# RGB_Video_Output.net
KiCad netlist of a schematic drawn in Altium Designer
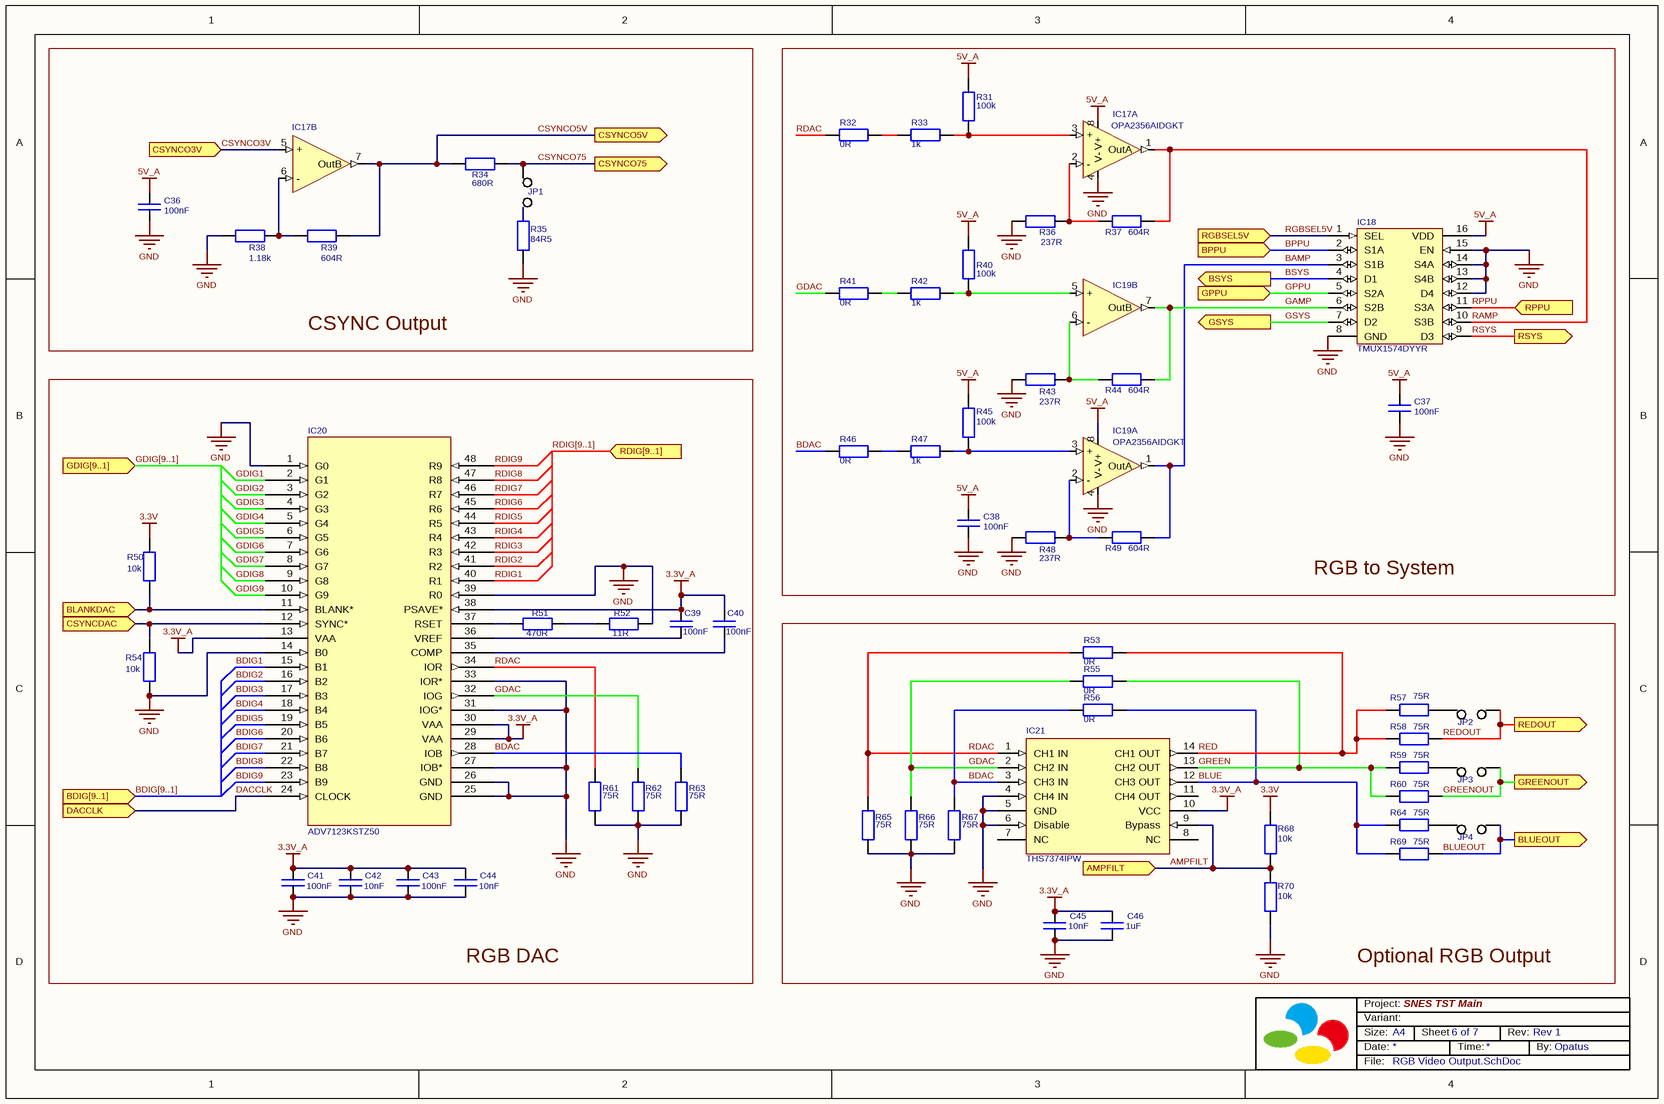
[diagram p0: RGB Video Output.SchDoc]

(export (version "E")
  (design (tool "Eeschema 10.0.6"))
  (components
    (comp (ref "C36")
      (value "100nF")
      (footprint "Cap_0402_Chip")
      (fields
        (field (name "TOLERANCE") "±20%")
        (field (name "Comment") "Ceramic Capacitor 100nF 10V ±20% X7R 0402")
      )
      (libsource (lib "PCB") (part "Capacitor"))
    )
    (comp (ref "C37")
      (value "100nF")
      (footprint "Cap_0402_Chip")
      (fields
        (field (name "TOLERANCE") "±20%")
        (field (name "Comment") "Ceramic Capacitor 100nF 10V ±20% X7R 0402")
      )
      (libsource (lib "PCB") (part "Capacitor"))
    )
    (comp (ref "C38")
      (value "100nF")
      (footprint "Cap_0402_Chip")
      (fields
        (field (name "TOLERANCE") "±20%")
        (field (name "Comment") "Ceramic Capacitor 100nF 10V ±20% X7R 0402")
      )
      (libsource (lib "PCB") (part "Capacitor"))
    )
    (comp (ref "C39")
      (value "100nF")
      (footprint "Cap_0402_Chip")
      (fields
        (field (name "TOLERANCE") "±20%")
        (field (name "Comment") "Ceramic Capacitor 100nF 10V ±20% X7R 0402")
      )
      (libsource (lib "PCB") (part "Capacitor"))
    )
    (comp (ref "C40")
      (value "100nF")
      (footprint "Cap_0402_Chip")
      (fields
        (field (name "TOLERANCE") "±20%")
        (field (name "Comment") "Ceramic Capacitor 100nF 10V ±20% X7R 0402")
      )
      (libsource (lib "PCB") (part "Capacitor"))
    )
    (comp (ref "C41")
      (value "100nF")
      (footprint "Cap_0402_Chip")
      (fields
        (field (name "TOLERANCE") "±20%")
        (field (name "Comment") "Ceramic Capacitor 100nF 10V ±20% X7R 0402")
      )
      (libsource (lib "PCB") (part "Capacitor"))
    )
    (comp (ref "C42")
      (value "10nF")
      (footprint "Cap_0402_Chip")
      (fields
        (field (name "TOLERANCE") "±20%")
        (field (name "Comment") "Ceramic Capacitor 10nF 10V ±20% X7R 0402")
      )
      (libsource (lib "PCB") (part "Capacitor"))
    )
    (comp (ref "C43")
      (value "100nF")
      (footprint "Cap_0402_Chip")
      (fields
        (field (name "TOLERANCE") "±20%")
        (field (name "Comment") "Ceramic Capacitor 100nF 10V ±20% X7R 0402")
      )
      (libsource (lib "PCB") (part "Capacitor"))
    )
    (comp (ref "C44")
      (value "10nF")
      (footprint "Cap_0402_Chip")
      (fields
        (field (name "TOLERANCE") "±20%")
        (field (name "Comment") "Ceramic Capacitor 10nF 10V ±20% X7R 0402")
      )
      (libsource (lib "PCB") (part "Capacitor"))
    )
    (comp (ref "C45")
      (value "10nF")
      (footprint "Cap_0402_Chip")
      (fields
        (field (name "TOLERANCE") "±20%")
        (field (name "Comment") "Ceramic Capacitor 10nF 10V ±20% X7R 0402")
      )
      (libsource (lib "PCB") (part "Capacitor"))
    )
    (comp (ref "C46")
      (value "1uF")
      (footprint "Cap_0603_Chip")
      (fields
        (field (name "TOLERANCE") "±20%")
        (field (name "Comment") "Ceramic Capacitor 1uF 10V ±20% X7R 0603")
      )
      (libsource (lib "PCB") (part "Capacitor"))
    )
    (comp (ref "IC17")
      (value "OPA2356")
      (footprint "MSOP8")
      (fields
        (field (name "MANUFACTURER") "Texas Instruments")
        (field (name "MANUFACTURER_PART_NUMBER") "OPA2356AIDGKT")
      )
      (libsource (lib "PCB") (part "OPA2356"))
    )
    (comp (ref "IC18")
      (value "TMUX1574")
      (footprint "SOT-23THIN16")
      (description "SPDT 4 Ch")
      (fields
        (field (name "MANUFACTURER") "Texas Instruments")
        (field (name "MANUFACTURER_PART_NUMBER") "TMUX1574DYYR")
      )
      (libsource (lib "PCB") (part "TMUX1574"))
    )
    (comp (ref "IC19")
      (value "OPA2356")
      (footprint "MSOP8")
      (fields
        (field (name "MANUFACTURER") "Texas Instruments")
        (field (name "MANUFACTURER_PART_NUMBER") "OPA2356AIDGKT")
      )
      (libsource (lib "PCB") (part "OPA2356"))
    )
    (comp (ref "IC20")
      (value "ADV7123")
      (footprint "ST_48_ADI")
      (description "10Bit Video DAC")
      (fields
        (field (name "MANUFACTURER") "Analog Devices Inc")
        (field (name "MANUFACTURER_PART_NUMBER") "ADV7123KSTZ50")
        (field (name "COPYRIGHT") "Copyright (C) 2018 Accelerated Designs. All rights reserved")
      )
      (libsource (lib "PCB") (part "ADV7123KSTZ140"))
    )
    (comp (ref "IC21")
      (value "THS7374")
      (footprint "TSSOP14")
      (fields
        (field (name "MANUFACTURER") "Texas Instruments")
        (field (name "MANUFACTURER_PART_NUMBER") "THS7374IPW")
      )
      (libsource (lib "PCB") (part "THS7374"))
    )
    (comp (ref "JP1") (value "Jumper") (footprint "Jumper") (libsource (lib "PCB") (part "Jumper")))
    (comp (ref "JP2") (value "Jumper") (footprint "Jumper") (libsource (lib "PCB") (part "Jumper")))
    (comp (ref "JP3") (value "Jumper") (footprint "Jumper") (libsource (lib "PCB") (part "Jumper")))
    (comp (ref "JP4") (value "Jumper") (footprint "Jumper") (libsource (lib "PCB") (part "Jumper")))
    (comp (ref "R31")
      (value "100k")
      (footprint "Res_0402_Chip")
      (fields (field (name "TOLERANCE") "±1%") (field (name "Comment") "Resistor 100k 0402 ±1%"))
      (libsource (lib "") (part "R_2"))
    )
    (comp (ref "R32")
      (value "0R")
      (footprint "Res_0402_Chip")
      (fields (field (name "Comment") "Resistor 0R 0402 "))
      (libsource (lib "PCB") (part "R"))
    )
    (comp (ref "R33")
      (value "1k")
      (footprint "Res_0402_Chip")
      (fields (field (name "TOLERANCE") "±1%") (field (name "Comment") "Resistor 1k 0402 ±1%"))
      (libsource (lib "PCB") (part "R"))
    )
    (comp (ref "R34")
      (value "680R")
      (footprint "Res_0603_Chip")
      (fields (field (name "TOLERANCE") "±1%") (field (name "Comment") "Resistor 680R 0603 ±1%"))
      (libsource (lib "") (part "R_1"))
    )
    (comp (ref "R35")
      (value "84R5")
      (footprint "Res_0402_Chip")
      (fields (field (name "TOLERANCE") "±1%") (field (name "Comment") "Resistor 84R5 0402 ±1%"))
      (libsource (lib "") (part "R_2"))
    )
    (comp (ref "R36")
      (value "237R")
      (footprint "Res_0402_Chip")
      (fields (field (name "TOLERANCE") "±1%") (field (name "Comment") "Resistor 237R 0402 ±1%"))
      (libsource (lib "") (part "R_1"))
    )
    (comp (ref "R37")
      (value "604R")
      (footprint "Res_0402_Chip")
      (fields (field (name "TOLERANCE") "±1%") (field (name "Comment") "Resistor 604R 0402 ±1%"))
      (libsource (lib "") (part "R_1"))
    )
    (comp (ref "R38")
      (value "1.18k")
      (footprint "Res_0402_Chip")
      (fields (field (name "TOLERANCE") "±1%") (field (name "Comment") "Resistor 1.18k 0402 ±1%"))
      (libsource (lib "") (part "R_1"))
    )
    (comp (ref "R39")
      (value "604R")
      (footprint "Res_0402_Chip")
      (fields (field (name "TOLERANCE") "±1%") (field (name "Comment") "Resistor 604R 0402 ±1%"))
      (libsource (lib "PCB") (part "R"))
    )
    (comp (ref "R40")
      (value "100k")
      (footprint "Res_0402_Chip")
      (fields (field (name "TOLERANCE") "±1%") (field (name "Comment") "Resistor 100k 0402 ±1%"))
      (libsource (lib "") (part "R_2"))
    )
    (comp (ref "R41")
      (value "0R")
      (footprint "Res_0402_Chip")
      (fields (field (name "Comment") "Resistor 0R 0402 "))
      (libsource (lib "PCB") (part "R"))
    )
    (comp (ref "R42")
      (value "1k")
      (footprint "Res_0402_Chip")
      (fields (field (name "TOLERANCE") "±1%") (field (name "Comment") "Resistor 1k 0402 ±1%"))
      (libsource (lib "PCB") (part "R"))
    )
    (comp (ref "R43")
      (value "237R")
      (footprint "Res_0402_Chip")
      (fields (field (name "TOLERANCE") "±1%") (field (name "Comment") "Resistor 237R 0402 ±1%"))
      (libsource (lib "") (part "R_1"))
    )
    (comp (ref "R44")
      (value "604R")
      (footprint "Res_0402_Chip")
      (fields (field (name "TOLERANCE") "±1%") (field (name "Comment") "Resistor 604R 0402 ±1%"))
      (libsource (lib "PCB") (part "R"))
    )
    (comp (ref "R45")
      (value "100k")
      (footprint "Res_0402_Chip")
      (fields (field (name "TOLERANCE") "±1%") (field (name "Comment") "Resistor 100k 0402 ±1%"))
      (libsource (lib "") (part "R_2"))
    )
    (comp (ref "R46")
      (value "0R")
      (footprint "Res_0402_Chip")
      (fields (field (name "Comment") "Resistor 0R 0402 "))
      (libsource (lib "PCB") (part "R"))
    )
    (comp (ref "R47")
      (value "1k")
      (footprint "Res_0402_Chip")
      (fields (field (name "TOLERANCE") "±1%") (field (name "Comment") "Resistor 1k 0402 ±1%"))
      (libsource (lib "PCB") (part "R"))
    )
    (comp (ref "R48")
      (value "237R")
      (footprint "Res_0402_Chip")
      (fields (field (name "TOLERANCE") "±1%") (field (name "Comment") "Resistor 237R 0402 ±1%"))
      (libsource (lib "PCB") (part "R"))
    )
    (comp (ref "R49")
      (value "604R")
      (footprint "Res_0402_Chip")
      (fields (field (name "TOLERANCE") "±1%") (field (name "Comment") "Resistor 604R 0402 ±1%"))
      (libsource (lib "") (part "R_1"))
    )
    (comp (ref "R50")
      (value "10k")
      (footprint "Res_0402_Chip")
      (fields (field (name "TOLERANCE") "±1%") (field (name "Comment") "Resistor 10k 0402 ±1%"))
      (libsource (lib "") (part "R_2"))
    )
    (comp (ref "R51")
      (value "470R")
      (footprint "Res_0402_Chip")
      (fields (field (name "TOLERANCE") "±1%") (field (name "Comment") "Resistor 470R 0402 ±1%"))
      (libsource (lib "") (part "R_1"))
    )
    (comp (ref "R52")
      (value "11R")
      (footprint "Res_0402_Chip")
      (fields (field (name "TOLERANCE") "±1%") (field (name "Comment") "Resistor 11R 0402 ±1%"))
      (libsource (lib "") (part "R_1"))
    )
    (comp (ref "R53")
      (value "0R")
      (footprint "Res_0402_Chip")
      (fields (field (name "Comment") "Resistor 0R 0402 "))
      (libsource (lib "PCB") (part "R"))
    )
    (comp (ref "R54")
      (value "10k")
      (footprint "Res_0402_Chip")
      (fields (field (name "TOLERANCE") "±1%") (field (name "Comment") "Resistor 10k 0402 ±1%"))
      (libsource (lib "") (part "R_2"))
    )
    (comp (ref "R55")
      (value "0R")
      (footprint "Res_0402_Chip")
      (fields (field (name "Comment") "Resistor 0R 0402 "))
      (libsource (lib "PCB") (part "R"))
    )
    (comp (ref "R56")
      (value "0R")
      (footprint "Res_0402_Chip")
      (fields (field (name "Comment") "Resistor 0R 0402 "))
      (libsource (lib "PCB") (part "R"))
    )
    (comp (ref "R57")
      (value "75R")
      (footprint "Res_0603_Chip")
      (fields (field (name "TOLERANCE") "±1%") (field (name "Comment") "Resistor 75R 0603 ±1%"))
      (libsource (lib "") (part "R_1"))
    )
    (comp (ref "R58")
      (value "75R")
      (footprint "Res_0603_Chip")
      (fields (field (name "TOLERANCE") "±1%") (field (name "Comment") "Resistor 75R 0603 ±1%"))
      (libsource (lib "") (part "R_1"))
    )
    (comp (ref "R59")
      (value "75R")
      (footprint "Res_0603_Chip")
      (fields (field (name "TOLERANCE") "±1%") (field (name "Comment") "Resistor 75R 0603 ±1%"))
      (libsource (lib "") (part "R_1"))
    )
    (comp (ref "R60")
      (value "75R")
      (footprint "Res_0603_Chip")
      (fields (field (name "TOLERANCE") "±1%") (field (name "Comment") "Resistor 75R 0603 ±1%"))
      (libsource (lib "") (part "R_1"))
    )
    (comp (ref "R61")
      (value "75R")
      (footprint "Res_0402_Chip")
      (fields (field (name "TOLERANCE") "±1%") (field (name "Comment") "Resistor 75R 0402 ±1%"))
      (libsource (lib "") (part "R_2"))
    )
    (comp (ref "R62")
      (value "75R")
      (footprint "Res_0402_Chip")
      (fields (field (name "TOLERANCE") "±1%") (field (name "Comment") "Resistor 75R 0402 ±1%"))
      (libsource (lib "") (part "R_2"))
    )
    (comp (ref "R63")
      (value "75R")
      (footprint "Res_0402_Chip")
      (fields (field (name "TOLERANCE") "±1%") (field (name "Comment") "Resistor 75R 0402 ±1%"))
      (libsource (lib "") (part "R_2"))
    )
    (comp (ref "R64")
      (value "75R")
      (footprint "Res_0603_Chip")
      (fields (field (name "TOLERANCE") "±1%") (field (name "Comment") "Resistor 75R 0603 ±1%"))
      (libsource (lib "") (part "R_1"))
    )
    (comp (ref "R65")
      (value "75R")
      (footprint "Res_0402_Chip")
      (fields (field (name "TOLERANCE") "±1%") (field (name "Comment") "Resistor 75R 0402 ±1%"))
      (libsource (lib "") (part "R_2"))
    )
    (comp (ref "R66")
      (value "75R")
      (footprint "Res_0402_Chip")
      (fields (field (name "TOLERANCE") "±1%") (field (name "Comment") "Resistor 75R 0402 ±1%"))
      (libsource (lib "") (part "R_2"))
    )
    (comp (ref "R67")
      (value "75R")
      (footprint "Res_0402_Chip")
      (fields (field (name "TOLERANCE") "±1%") (field (name "Comment") "Resistor 75R 0402 ±1%"))
      (libsource (lib "") (part "R_2"))
    )
    (comp (ref "R68")
      (value "10k")
      (footprint "Res_0402_Chip")
      (fields (field (name "TOLERANCE") "±1%") (field (name "Comment") "Resistor 10k 0402 ±1%"))
      (libsource (lib "") (part "R_3"))
    )
    (comp (ref "R69")
      (value "75R")
      (footprint "Res_0603_Chip")
      (fields (field (name "TOLERANCE") "±1%") (field (name "Comment") "Resistor 75R 0603 ±1%"))
      (libsource (lib "") (part "R_1"))
    )
    (comp (ref "R70")
      (value "10k")
      (footprint "Res_0402_Chip")
      (fields (field (name "TOLERANCE") "±1%") (field (name "Comment") "Resistor 10k 0402 ±1%"))
      (libsource (lib "") (part "R_3"))
    )
  )
  (nets
    (net (code "1") (name "/AMPFILT") (class "Default")
      (node (ref "IC21") (pin "9") (pinfunction "Bypass_9") (pintype "input"))
      (node (ref "R68") (pin "2") (pintype "passive"))
      (node (ref "R70") (pin "1") (pintype "passive"))
    )
    (net (code "2") (name "/BAMP") (class "Default")
      (node (ref "IC18") (pin "3") (pinfunction "S1B_3") (pintype "bidirectional"))
      (node (ref "IC19") (pin "1") (pinfunction "OutA_1") (pintype "output"))
      (node (ref "R49") (pin "2") (pintype "passive"))
    )
    (net (code "3") (name "/BDAC") (class "Default")
      (node (ref "IC20") (pin "28") (pinfunction "IOB_28") (pintype "output"))
      (node (ref "IC21") (pin "3") (pinfunction "CH3_IN_3") (pintype "input"))
      (node (ref "R46") (pin "2") (pintype "passive"))
      (node (ref "R56") (pin "2") (pintype "passive"))
      (node (ref "R63") (pin "2") (pintype "passive"))
      (node (ref "R67") (pin "2") (pintype "passive"))
    )
    (net (code "4") (name "/BDIG1") (class "Default")
      (node (ref "IC20") (pin "15") (pinfunction "B1_15") (pintype "input"))
    )
    (net (code "5") (name "/BDIG2") (class "Default")
      (node (ref "IC20") (pin "16") (pinfunction "B2_16") (pintype "input"))
    )
    (net (code "6") (name "/BDIG3") (class "Default")
      (node (ref "IC20") (pin "17") (pinfunction "B3_17") (pintype "input"))
    )
    (net (code "7") (name "/BDIG4") (class "Default")
      (node (ref "IC20") (pin "18") (pinfunction "B4_18") (pintype "input"))
    )
    (net (code "8") (name "/BDIG5") (class "Default")
      (node (ref "IC20") (pin "19") (pinfunction "B5_19") (pintype "input"))
    )
    (net (code "9") (name "/BDIG6") (class "Default")
      (node (ref "IC20") (pin "20") (pinfunction "B6_20") (pintype "input"))
    )
    (net (code "10") (name "/BDIG7") (class "Default")
      (node (ref "IC20") (pin "21") (pinfunction "B7_21") (pintype "input"))
    )
    (net (code "11") (name "/BDIG8") (class "Default")
      (node (ref "IC20") (pin "22") (pinfunction "B8_22") (pintype "input"))
    )
    (net (code "12") (name "/BDIG9") (class "Default")
      (node (ref "IC20") (pin "23") (pinfunction "B9_23") (pintype "input"))
    )
    (net (code "14") (name "/BLANKDAC") (class "Default")
      (node (ref "IC20") (pin "11") (pinfunction "BLANK*_11") (pintype "input"))
      (node (ref "R50") (pin "1") (pintype "passive"))
    )
    (net (code "15") (name "/BLUE") (class "Default")
      (node (ref "IC21") (pin "12") (pinfunction "CH3_OUT_12") (pintype "output"))
      (node (ref "R56") (pin "1") (pintype "passive"))
      (node (ref "R64") (pin "1") (pintype "passive"))
      (node (ref "R69") (pin "1") (pintype "passive"))
    )
    (net (code "16") (name "/BLUEOUT") (class "Default")
      (node (ref "JP4") (pin "1") (pinfunction "0_1") (pintype "passive"))
      (node (ref "R69") (pin "2") (pintype "passive"))
    )
    (net (code "17") (name "/BPPU") (class "Default")
      (node (ref "IC18") (pin "2") (pinfunction "S1A_2") (pintype "bidirectional"))
    )
    (net (code "18") (name "/BSYS") (class "Default")
      (node (ref "IC18") (pin "4") (pinfunction "D1_4") (pintype "bidirectional"))
    )
    (net (code "19") (name "/CSYNCDAC") (class "Default")
      (node (ref "IC20") (pin "12") (pinfunction "SYNC*_12") (pintype "input"))
      (node (ref "R54") (pin "2") (pintype "passive"))
    )
    (net (code "20") (name "/CSYNCO3V") (class "Default")
      (node (ref "IC17") (pin "5") (pinfunction "+_5") (pintype "input"))
    )
    (net (code "21") (name "/CSYNCO5V") (class "Default")
      (node (ref "IC17") (pin "7") (pinfunction "OutB_7") (pintype "output"))
      (node (ref "R34") (pin "1") (pintype "passive"))
      (node (ref "R39") (pin "1") (pintype "passive"))
    )
    (net (code "22") (name "/CSYNCO75") (class "Default")
      (node (ref "JP1") (pin "1") (pinfunction "0_1") (pintype "passive"))
      (node (ref "R34") (pin "2") (pintype "passive"))
    )
    (net (code "23") (name "/DACCLK") (class "Default")
      (node (ref "IC20") (pin "24") (pinfunction "CLOCK_24") (pintype "input"))
    )
    (net (code "24") (name "/GAMP") (class "Default")
      (node (ref "IC18") (pin "6") (pinfunction "S2B_6") (pintype "bidirectional"))
      (node (ref "IC19") (pin "7") (pinfunction "OutB_7") (pintype "output"))
      (node (ref "R44") (pin "1") (pintype "passive"))
    )
    (net (code "25") (name "/GDAC") (class "Default")
      (node (ref "IC20") (pin "32") (pinfunction "IOG_32") (pintype "output"))
      (node (ref "IC21") (pin "2") (pinfunction "CH2_IN_2") (pintype "input"))
      (node (ref "R41") (pin "2") (pintype "passive"))
      (node (ref "R55") (pin "2") (pintype "passive"))
      (node (ref "R62") (pin "2") (pintype "passive"))
      (node (ref "R66") (pin "2") (pintype "passive"))
    )
    (net (code "26") (name "/GDIG1") (class "Default")
      (node (ref "IC20") (pin "2") (pinfunction "G1_2") (pintype "input"))
    )
    (net (code "27") (name "/GDIG2") (class "Default")
      (node (ref "IC20") (pin "3") (pinfunction "G2_3") (pintype "input"))
    )
    (net (code "28") (name "/GDIG3") (class "Default")
      (node (ref "IC20") (pin "4") (pinfunction "G3_4") (pintype "input"))
    )
    (net (code "29") (name "/GDIG4") (class "Default")
      (node (ref "IC20") (pin "5") (pinfunction "G4_5") (pintype "input"))
    )
    (net (code "30") (name "/GDIG5") (class "Default")
      (node (ref "IC20") (pin "6") (pinfunction "G5_6") (pintype "input"))
    )
    (net (code "31") (name "/GDIG6") (class "Default")
      (node (ref "IC20") (pin "7") (pinfunction "G6_7") (pintype "input"))
    )
    (net (code "32") (name "/GDIG7") (class "Default")
      (node (ref "IC20") (pin "8") (pinfunction "G7_8") (pintype "input"))
    )
    (net (code "33") (name "/GDIG8") (class "Default")
      (node (ref "IC20") (pin "9") (pinfunction "G8_9") (pintype "input"))
    )
    (net (code "34") (name "/GDIG9") (class "Default")
      (node (ref "IC20") (pin "10") (pinfunction "G9_10") (pintype "input"))
    )
    (net (code "36") (name "/GPPU") (class "Default")
      (node (ref "IC18") (pin "5") (pinfunction "S2A_5") (pintype "bidirectional"))
    )
    (net (code "37") (name "/GREEN") (class "Default")
      (node (ref "IC21") (pin "13") (pinfunction "CH2_OUT_13") (pintype "output"))
      (node (ref "R55") (pin "1") (pintype "passive"))
      (node (ref "R59") (pin "1") (pintype "passive"))
      (node (ref "R60") (pin "1") (pintype "passive"))
    )
    (net (code "38") (name "/GREENOUT") (class "Default")
      (node (ref "JP3") (pin "1") (pinfunction "0_1") (pintype "passive"))
      (node (ref "R60") (pin "2") (pintype "passive"))
    )
    (net (code "39") (name "/GSYS") (class "Default")
      (node (ref "IC18") (pin "7") (pinfunction "D2_7") (pintype "bidirectional"))
    )
    (net (code "40") (name "/RAMP") (class "Default")
      (node (ref "IC17") (pin "1") (pinfunction "OutA_1") (pintype "output"))
      (node (ref "IC18") (pin "10") (pinfunction "S3B_10") (pintype "bidirectional"))
      (node (ref "R37") (pin "2") (pintype "passive"))
    )
    (net (code "41") (name "/RDAC") (class "Default")
      (node (ref "IC20") (pin "34") (pinfunction "IOR_34") (pintype "output"))
      (node (ref "IC21") (pin "1") (pinfunction "CH1_IN_1") (pintype "input"))
      (node (ref "R32") (pin "2") (pintype "passive"))
      (node (ref "R53") (pin "2") (pintype "passive"))
      (node (ref "R61") (pin "2") (pintype "passive"))
      (node (ref "R65") (pin "2") (pintype "passive"))
    )
    (net (code "42") (name "/RDIG1") (class "Default")
      (node (ref "IC20") (pin "40") (pinfunction "R1_40") (pintype "input"))
    )
    (net (code "43") (name "/RDIG2") (class "Default")
      (node (ref "IC20") (pin "41") (pinfunction "R2_41") (pintype "input"))
    )
    (net (code "44") (name "/RDIG3") (class "Default")
      (node (ref "IC20") (pin "42") (pinfunction "R3_42") (pintype "input"))
    )
    (net (code "45") (name "/RDIG4") (class "Default")
      (node (ref "IC20") (pin "43") (pinfunction "R4_43") (pintype "input"))
    )
    (net (code "46") (name "/RDIG5") (class "Default")
      (node (ref "IC20") (pin "44") (pinfunction "R5_44") (pintype "input"))
    )
    (net (code "47") (name "/RDIG6") (class "Default")
      (node (ref "IC20") (pin "45") (pinfunction "R6_45") (pintype "input"))
    )
    (net (code "48") (name "/RDIG7") (class "Default")
      (node (ref "IC20") (pin "46") (pinfunction "R7_46") (pintype "input"))
    )
    (net (code "49") (name "/RDIG8") (class "Default")
      (node (ref "IC20") (pin "47") (pinfunction "R8_47") (pintype "input"))
    )
    (net (code "50") (name "/RDIG9") (class "Default")
      (node (ref "IC20") (pin "48") (pinfunction "R9_48") (pintype "input"))
    )
    (net (code "52") (name "/RED") (class "Default")
      (node (ref "IC21") (pin "14") (pinfunction "CH1_OUT_14") (pintype "output"))
      (node (ref "R53") (pin "1") (pintype "passive"))
      (node (ref "R57") (pin "1") (pintype "passive"))
      (node (ref "R58") (pin "1") (pintype "passive"))
    )
    (net (code "53") (name "/REDOUT") (class "Default")
      (node (ref "JP2") (pin "1") (pinfunction "0_1") (pintype "passive"))
      (node (ref "R58") (pin "2") (pintype "passive"))
    )
    (net (code "54") (name "/RGBSEL5V") (class "Default")
      (node (ref "IC18") (pin "1") (pinfunction "SEL_1") (pintype "input"))
    )
    (net (code "55") (name "/RPPU") (class "Default")
      (node (ref "IC18") (pin "11") (pinfunction "S3A_11") (pintype "bidirectional"))
    )
    (net (code "56") (name "/RSYS") (class "Default")
      (node (ref "IC18") (pin "9") (pinfunction "D3_9") (pintype "bidirectional"))
    )
    (net (code "57") (name "3.3V") (class "Default")
      (node (ref "R50") (pin "2") (pintype "passive"))
      (node (ref "R68") (pin "1") (pintype "passive"))
    )
    (net (code "58") (name "3.3V_A") (class "Default")
      (node (ref "C39") (pin "1") (pintype "passive"))
      (node (ref "C40") (pin "1") (pintype "passive"))
      (node (ref "C41") (pin "2") (pintype "passive"))
      (node (ref "C42") (pin "2") (pintype "passive"))
      (node (ref "C43") (pin "2") (pintype "passive"))
      (node (ref "C44") (pin "2") (pintype "passive"))
      (node (ref "C45") (pin "2") (pintype "passive"))
      (node (ref "C46") (pin "2") (pintype "passive"))
      (node (ref "IC20") (pin "13") (pinfunction "VAA_13") (pintype "power_in"))
      (node (ref "IC20") (pin "29") (pinfunction "VAA_29") (pintype "power_in"))
      (node (ref "IC20") (pin "30") (pinfunction "VAA_30") (pintype "power_in"))
      (node (ref "IC20") (pin "38") (pinfunction "PSAVE*_38") (pintype "input"))
      (node (ref "IC21") (pin "10") (pinfunction "VCC_10") (pintype "power_in"))
    )
    (net (code "59") (name "5V_A") (class "Default")
      (node (ref "C36") (pin "1") (pintype "passive"))
      (node (ref "C37") (pin "1") (pintype "passive"))
      (node (ref "C38") (pin "1") (pintype "passive"))
      (node (ref "IC17") (pin "8") (pinfunction "V+_8") (pintype "power_in"))
      (node (ref "IC18") (pin "16") (pinfunction "VDD_16") (pintype "power_in"))
      (node (ref "IC19") (pin "8") (pinfunction "V+_8") (pintype "power_in"))
      (node (ref "R31") (pin "2") (pintype "passive"))
      (node (ref "R40") (pin "2") (pintype "passive"))
      (node (ref "R45") (pin "2") (pintype "passive"))
    )
    (net (code "60") (name "GND") (class "Default")
      (node (ref "C36") (pin "2") (pintype "passive"))
      (node (ref "C37") (pin "2") (pintype "passive"))
      (node (ref "C38") (pin "2") (pintype "passive"))
      (node (ref "C41") (pin "1") (pintype "passive"))
      (node (ref "C42") (pin "1") (pintype "passive"))
      (node (ref "C43") (pin "1") (pintype "passive"))
      (node (ref "C44") (pin "1") (pintype "passive"))
      (node (ref "C45") (pin "1") (pintype "passive"))
      (node (ref "C46") (pin "1") (pintype "passive"))
      (node (ref "IC17") (pin "4") (pinfunction "V-_4") (pintype "power_in"))
      (node (ref "IC18") (pin "12") (pinfunction "D4_12") (pintype "bidirectional"))
      (node (ref "IC18") (pin "13") (pinfunction "S4B_13") (pintype "bidirectional"))
      (node (ref "IC18") (pin "14") (pinfunction "S4A_14") (pintype "bidirectional"))
      (node (ref "IC18") (pin "15") (pinfunction "EN_15") (pintype "input"))
      (node (ref "IC18") (pin "8") (pinfunction "GND_8") (pintype "power_in"))
      (node (ref "IC19") (pin "4") (pinfunction "V-_4") (pintype "power_in"))
      (node (ref "IC20") (pin "1") (pinfunction "G0_1") (pintype "input"))
      (node (ref "IC20") (pin "14") (pinfunction "B0_14") (pintype "input"))
      (node (ref "IC20") (pin "25") (pinfunction "GND_25") (pintype "power_in"))
      (node (ref "IC20") (pin "26") (pinfunction "GND_26") (pintype "power_in"))
      (node (ref "IC20") (pin "27") (pinfunction "IOB*_27") (pintype "passive"))
      (node (ref "IC20") (pin "31") (pinfunction "IOG*_31") (pintype "passive"))
      (node (ref "IC20") (pin "33") (pinfunction "IOR*_33") (pintype "passive"))
      (node (ref "IC20") (pin "39") (pinfunction "R0_39") (pintype "input"))
      (node (ref "IC21") (pin "4") (pinfunction "CH4_IN_4") (pintype "input"))
      (node (ref "IC21") (pin "5") (pinfunction "GND_5") (pintype "power_in"))
      (node (ref "IC21") (pin "6") (pinfunction "Disable_6") (pintype "input"))
      (node (ref "R35") (pin "1") (pintype "passive"))
      (node (ref "R36") (pin "1") (pintype "passive"))
      (node (ref "R38") (pin "1") (pintype "passive"))
      (node (ref "R43") (pin "1") (pintype "passive"))
      (node (ref "R48") (pin "2") (pintype "passive"))
      (node (ref "R52") (pin "2") (pintype "passive"))
      (node (ref "R54") (pin "1") (pintype "passive"))
      (node (ref "R61") (pin "1") (pintype "passive"))
      (node (ref "R62") (pin "1") (pintype "passive"))
      (node (ref "R63") (pin "1") (pintype "passive"))
      (node (ref "R65") (pin "1") (pintype "passive"))
      (node (ref "R66") (pin "1") (pintype "passive"))
      (node (ref "R67") (pin "1") (pintype "passive"))
      (node (ref "R70") (pin "2") (pintype "passive"))
    )
    (net (code "61") (name "Net-(IC17A-+)") (class "Default")
      (node (ref "IC17") (pin "3") (pinfunction "+_3") (pintype "input"))
      (node (ref "R31") (pin "1") (pintype "passive"))
      (node (ref "R33") (pin "1") (pintype "passive"))
    )
    (net (code "62") (name "Net-(IC17A--)") (class "Default")
      (node (ref "IC17") (pin "2") (pinfunction "-_2") (pintype "input"))
      (node (ref "R36") (pin "2") (pintype "passive"))
      (node (ref "R37") (pin "1") (pintype "passive"))
    )
    (net (code "63") (name "Net-(IC17B--)") (class "Default")
      (node (ref "IC17") (pin "6") (pinfunction "-_6") (pintype "input"))
      (node (ref "R38") (pin "2") (pintype "passive"))
      (node (ref "R39") (pin "2") (pintype "passive"))
    )
    (net (code "64") (name "Net-(IC19A-+)") (class "Default")
      (node (ref "IC19") (pin "3") (pinfunction "+_3") (pintype "input"))
      (node (ref "R45") (pin "1") (pintype "passive"))
      (node (ref "R47") (pin "1") (pintype "passive"))
    )
    (net (code "65") (name "Net-(IC19A--)") (class "Default")
      (node (ref "IC19") (pin "2") (pinfunction "-_2") (pintype "input"))
      (node (ref "R48") (pin "1") (pintype "passive"))
      (node (ref "R49") (pin "1") (pintype "passive"))
    )
    (net (code "66") (name "Net-(IC19B-+)") (class "Default")
      (node (ref "IC19") (pin "5") (pinfunction "+_5") (pintype "input"))
      (node (ref "R40") (pin "1") (pintype "passive"))
      (node (ref "R42") (pin "1") (pintype "passive"))
    )
    (net (code "67") (name "Net-(IC19B--)") (class "Default")
      (node (ref "IC19") (pin "6") (pinfunction "-_6") (pintype "input"))
      (node (ref "R43") (pin "2") (pintype "passive"))
      (node (ref "R44") (pin "2") (pintype "passive"))
    )
    (net (code "68") (name "Net-(IC20-COMP)") (class "Default")
      (node (ref "C40") (pin "2") (pintype "passive"))
      (node (ref "IC20") (pin "35") (pinfunction "COMP_35") (pintype "passive"))
    )
    (net (code "69") (name "Net-(IC20-RSET)") (class "Default")
      (node (ref "IC20") (pin "37") (pinfunction "RSET_37") (pintype "passive"))
      (node (ref "R51") (pin "1") (pintype "passive"))
    )
    (net (code "70") (name "Net-(IC20-VREF)") (class "Default")
      (node (ref "C39") (pin "2") (pintype "passive"))
      (node (ref "IC20") (pin "36") (pinfunction "VREF_36") (pintype "passive"))
    )
    (net (code "71") (name "Net-(JP1-0-Pad2)") (class "Default")
      (node (ref "JP1") (pin "2") (pinfunction "0_2") (pintype "passive"))
      (node (ref "R35") (pin "2") (pintype "passive"))
    )
    (net (code "72") (name "Net-(JP2-0-Pad2)") (class "Default")
      (node (ref "JP2") (pin "2") (pinfunction "0_2") (pintype "passive"))
      (node (ref "R57") (pin "2") (pintype "passive"))
    )
    (net (code "73") (name "Net-(JP3-0-Pad2)") (class "Default")
      (node (ref "JP3") (pin "2") (pinfunction "0_2") (pintype "passive"))
      (node (ref "R59") (pin "2") (pintype "passive"))
    )
    (net (code "74") (name "Net-(JP4-0-Pad2)") (class "Default")
      (node (ref "JP4") (pin "2") (pinfunction "0_2") (pintype "passive"))
      (node (ref "R64") (pin "2") (pintype "passive"))
    )
    (net (code "75") (name "Net-(R32-Pad1)") (class "Default")
      (node (ref "R32") (pin "1") (pintype "passive"))
      (node (ref "R33") (pin "2") (pintype "passive"))
    )
    (net (code "76") (name "Net-(R41-Pad1)") (class "Default")
      (node (ref "R41") (pin "1") (pintype "passive"))
      (node (ref "R42") (pin "2") (pintype "passive"))
    )
    (net (code "77") (name "Net-(R46-Pad1)") (class "Default")
      (node (ref "R46") (pin "1") (pintype "passive"))
      (node (ref "R47") (pin "2") (pintype "passive"))
    )
    (net (code "78") (name "Net-(R51-Pad2)") (class "Default")
      (node (ref "R51") (pin "2") (pintype "passive"))
      (node (ref "R52") (pin "1") (pintype "passive"))
    )
    (net (code "79") (name "unconnected-(IC21-CH4_OUT-Pad11)") (class "Default")
      (node (ref "IC21") (pin "11") (pinfunction "CH4_OUT_11") (pintype "output"))
    )
    (net (code "80") (name "unconnected-(IC21-NC-Pad7)") (class "Default")
      (node (ref "IC21") (pin "7") (pinfunction "NC_7") (pintype "passive"))
    )
    (net (code "81") (name "unconnected-(IC21-NC-Pad8)") (class "Default")
      (node (ref "IC21") (pin "8") (pinfunction "NC_8") (pintype "passive"))
    )
  )
)
